# ST_LINK_V2.net
KiCad netlist of a schematic drawn in Altium Designer
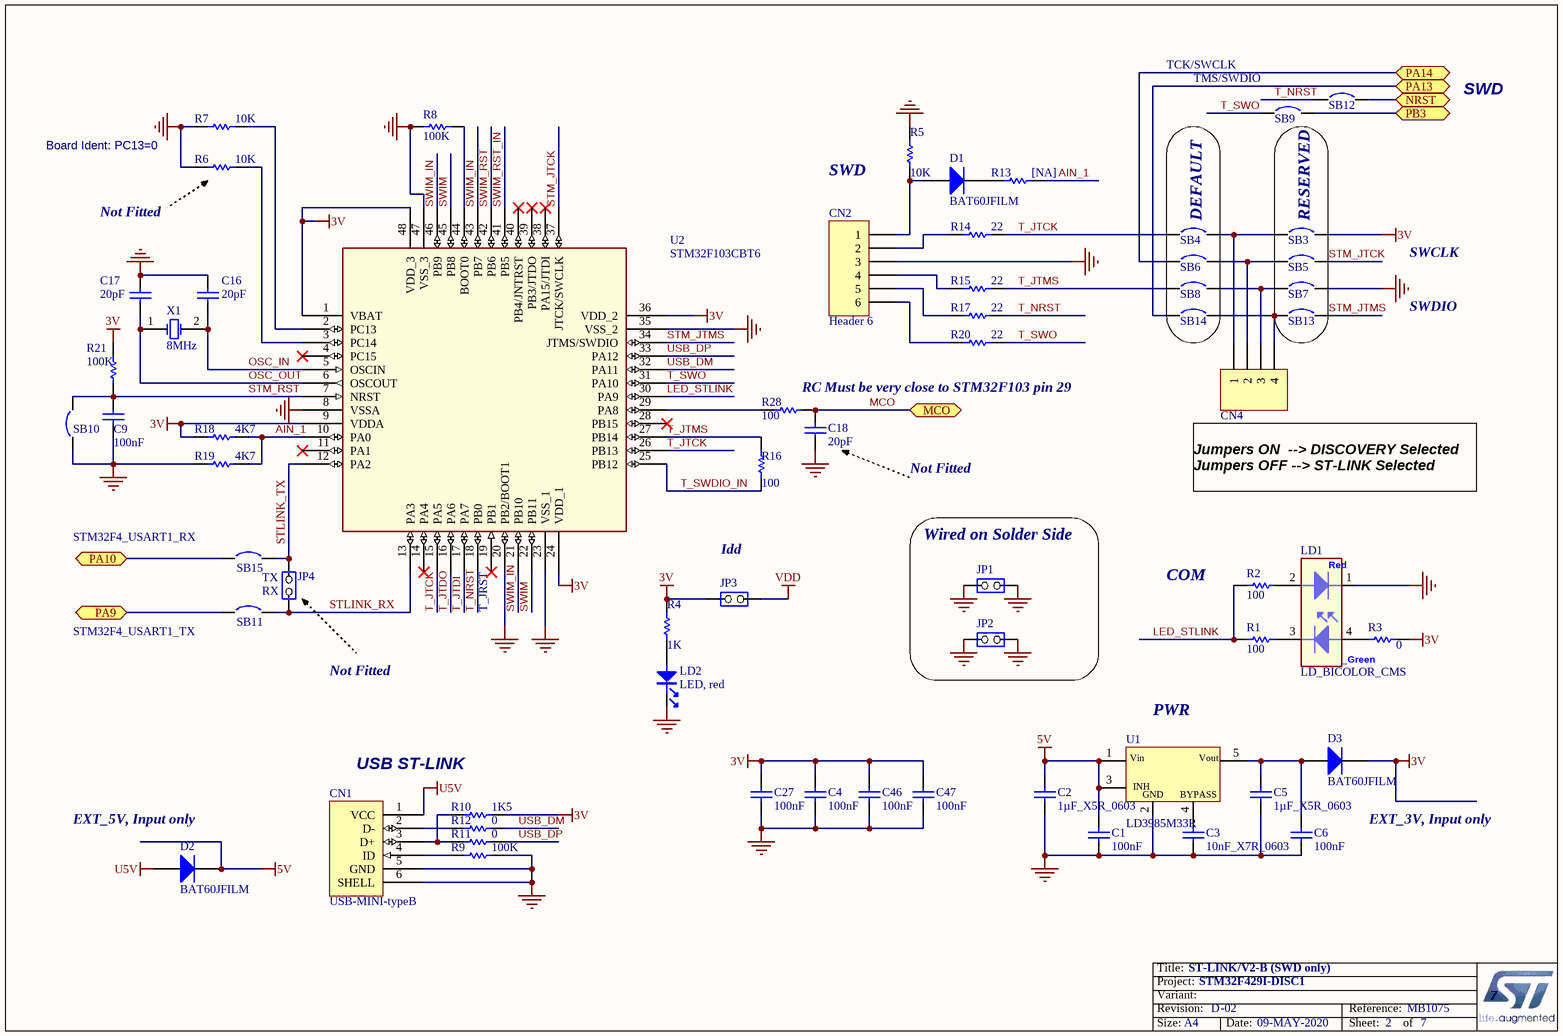
[diagram p0: ST_LINK_V2.SCHDOC]

(export (version "E")
  (design (tool "Eeschema 10.0.6"))
  (components
    (comp (ref "C1")
      (value "100nF")
      (footprint "0402C")
      (description "Capacitor 0402 / 0603 / 0805")
      (libsource (lib "MCD_TOOLS") (part "Capacitor_ST"))
    )
    (comp (ref "C2")
      (value "1µF_X5R_0603")
      (footprint "0603C")
      (description "0603  X5R 1µF")
      (fields (field (name "TOLERANCE") "10%"))
      (libsource (lib "MB963_1") (part "CAP SMD 0603  X5R 1µF 25V 10%"))
    )
    (comp (ref "C3")
      (value "10nF_X7R_0603")
      (footprint "0603C")
      (description "0603  X7R 10NF")
      (fields (field (name "TOLERANCE") "10%"))
      (libsource (lib "MB963_1") (part "CAP SMD 0603  X7R 10000PF 50V 10%"))
    )
    (comp (ref "C4")
      (value "100nF")
      (footprint "0402C")
      (description "Capacitor 0402 / 0603 / 0805")
      (libsource (lib "MCD_TOOLS") (part "Capacitor_ST"))
    )
    (comp (ref "C5")
      (value "1µF_X5R_0603")
      (footprint "0603C")
      (description "0603  X5R 1µF")
      (fields (field (name "TOLERANCE") "10%"))
      (libsource (lib "MB963_1") (part "CAP SMD 0603  X5R 1µF 25V 10%"))
    )
    (comp (ref "C6")
      (value "100nF")
      (footprint "0402C")
      (description "Capacitor 0402 / 0603 / 0805")
      (libsource (lib "MCD_TOOLS") (part "Capacitor_ST"))
    )
    (comp (ref "C9")
      (value "100nF")
      (footprint "0402C")
      (description "Capacitor 0402 / 0603 / 0805")
      (libsource (lib "MCD_TOOLS") (part "Capacitor_ST"))
    )
    (comp (ref "C16")
      (value "20pF")
      (footprint "0402C")
      (description "Capacitor 0402 / 0603 / 0805")
      (libsource (lib "MCD_TOOLS") (part "Capacitor_ST"))
    )
    (comp (ref "C17")
      (value "20pF")
      (footprint "0402C")
      (description "Capacitor 0402 / 0603 / 0805")
      (libsource (lib "MCD_TOOLS") (part "Capacitor_ST"))
    )
    (comp (ref "C18")
      (value "20pF")
      (footprint "0402C")
      (description "Capacitor 0402 / 0603 / 0805")
      (libsource (lib "MCD_TOOLS") (part "Capacitor_ST"))
    )
    (comp (ref "C27")
      (value "100nF")
      (footprint "0402C")
      (description "Capacitor 0402 / 0603 / 0805")
      (libsource (lib "MCD_TOOLS") (part "Capacitor_ST"))
    )
    (comp (ref "C46")
      (value "100nF")
      (footprint "0402C")
      (description "Capacitor 0402 / 0603 / 0805")
      (libsource (lib "MCD_TOOLS") (part "Capacitor_ST"))
    )
    (comp (ref "C47")
      (value "100nF")
      (footprint "0402C")
      (description "Capacitor 0402 / 0603 / 0805")
      (libsource (lib "MCD_TOOLS") (part "Capacitor_ST"))
    )
    (comp (ref "CN1")
      (value "USB-MINI-typeB")
      (footprint "USB-MINI-B-SMD")
      (description "USB-MINI-typeB connector")
      (libsource (lib "MCD_TOOLS") (part "USB-MINI-typeB connector"))
    )
    (comp (ref "CN2")
      (value "Header 6")
      (footprint "HDR1X6")
      (description "Header, 6-Pin")
      (fields (field (name "PUBLISHER") "Altium Limited"))
      (libsource (lib "Miscellaneous Connectors") (part "Header 6"))
    )
    (comp (ref "CN4")
      (value "Header 4")
      (footprint "Header 4")
      (description "Header, 4-Pin")
      (fields (field (name "PUBLISHER") "Altium Limited"))
      (libsource (lib "MB963_1") (part "Header 4"))
    )
    (comp (ref "D1")
      (value "BAT60JFILM")
      (footprint "SOD323/A")
      (libsource (lib "MCD_TOOLS") (part "BAT60JFILM"))
    )
    (comp (ref "D2")
      (value "BAT60JFILM")
      (footprint "SOD323/A")
      (libsource (lib "MCD_TOOLS") (part "BAT60JFILM"))
    )
    (comp (ref "D3")
      (value "BAT60JFILM")
      (footprint "SOD323/A")
      (libsource (lib "MCD_TOOLS") (part "BAT60JFILM"))
    )
    (comp (ref "JP1") (value "~") (footprint "SIP2/2.54") (libsource (lib "*") (part "JP2")))
    (comp (ref "JP2") (value "~") (footprint "SIP2/2.54") (libsource (lib "*") (part "JP2")))
    (comp (ref "JP3") (value "~") (footprint "SIP2/2.54") (libsource (lib "*") (part "JP2")))
    (comp (ref "JP4") (value "JP2") (footprint "SIP2/2.54") (libsource (lib "MCD_TOOLS") (part "JP2")))
    (comp (ref "LD1")
      (value "LD_BICOLOR_CMS")
      (footprint "HSMF-A201")
      (description "Bicolor Led")
      (libsource (lib "MCD_TOOLS") (part "LD_BICOLOR_CMS"))
    )
    (comp (ref "LD2")
      (value "LED, red")
      (footprint "0603D")
      (description "LED, red, 0603")
      (libsource (lib "MCD_TOOLS") (part "LED_red"))
    )
    (comp (ref "R1")
      (value "100")
      (footprint "0402R")
      (description "Resistor 0402 / 0603 / 0805")
      (libsource (lib "MCD_TOOLS") (part "Resistor_ST"))
    )
    (comp (ref "R2")
      (value "100")
      (footprint "0402R")
      (description "Resistor 0402 / 0603 / 0805")
      (libsource (lib "MCD_TOOLS") (part "Resistor_ST"))
    )
    (comp (ref "R3")
      (value "0")
      (footprint "0402R")
      (description "Resistor 0402 / 0603 / 0805")
      (libsource (lib "MCD_TOOLS") (part "Resistor_ST"))
    )
    (comp (ref "R4")
      (value "1K")
      (footprint "0402R")
      (description "Resistor 0402 / 0603 / 0805")
      (libsource (lib "MCD_TOOLS") (part "Resistor_ST"))
    )
    (comp (ref "R5")
      (value "10K")
      (footprint "0402R")
      (description "Resistor 0402 / 0603 / 0805")
      (libsource (lib "MCD_TOOLS") (part "Resistor_ST"))
    )
    (comp (ref "R6")
      (value "10K")
      (footprint "0402R")
      (description "Resistor 0402 / 0603 / 0805")
      (libsource (lib "MCD_TOOLS") (part "Resistor_ST"))
    )
    (comp (ref "R7")
      (value "10K")
      (footprint "0402R")
      (description "Resistor 0402 / 0603 / 0805")
      (libsource (lib "MCD_TOOLS") (part "Resistor_ST"))
    )
    (comp (ref "R8")
      (value "100K")
      (footprint "0402R")
      (description "Resistor 0402 / 0603 / 0805")
      (libsource (lib "MCD_TOOLS") (part "Resistor_ST"))
    )
    (comp (ref "R9")
      (value "100K")
      (footprint "0402R")
      (description "Resistor 0402 / 0603 / 0805")
      (libsource (lib "MCD_TOOLS") (part "Resistor_ST"))
    )
    (comp (ref "R10")
      (value "1K5")
      (footprint "0402R")
      (description "Resistor 0402 / 0603 / 0805")
      (libsource (lib "MCD_TOOLS") (part "Resistor_ST"))
    )
    (comp (ref "R11")
      (value "0")
      (footprint "0402R")
      (description "Resistor 0402 / 0603 / 0805")
      (libsource (lib "MCD_TOOLS") (part "Resistor_ST"))
    )
    (comp (ref "R12")
      (value "0")
      (footprint "0402R")
      (description "Resistor 0402 / 0603 / 0805")
      (libsource (lib "MCD_TOOLS") (part "Resistor_ST"))
    )
    (comp (ref "R13")
      (value "[NA]")
      (footprint "0402R")
      (description "Resistor 0402 / 0603 / 0805")
      (libsource (lib "MCD_TOOLS") (part "Resistor_ST"))
    )
    (comp (ref "R14")
      (value "22")
      (footprint "0402R")
      (description "Resistor 0402 / 0603 / 0805")
      (libsource (lib "MCD_TOOLS") (part "Resistor_ST"))
    )
    (comp (ref "R15")
      (value "22")
      (footprint "0402R")
      (description "Resistor 0402 / 0603 / 0805")
      (libsource (lib "MCD_TOOLS") (part "Resistor_ST"))
    )
    (comp (ref "R16")
      (value "100")
      (footprint "0402R")
      (description "Resistor 0402 / 0603 / 0805")
      (libsource (lib "MCD_TOOLS") (part "Resistor_ST"))
    )
    (comp (ref "R17")
      (value "22")
      (footprint "0402R")
      (description "Resistor 0402 / 0603 / 0805")
      (libsource (lib "MCD_TOOLS") (part "Resistor_ST"))
    )
    (comp (ref "R18")
      (value "4K7")
      (footprint "0402R")
      (description "Resistor 0402 / 0603 / 0805")
      (libsource (lib "MCD_TOOLS") (part "Resistor_ST"))
    )
    (comp (ref "R19")
      (value "4K7")
      (footprint "0402R")
      (description "Resistor 0402 / 0603 / 0805")
      (libsource (lib "MCD_TOOLS") (part "Resistor_ST"))
    )
    (comp (ref "R20")
      (value "22")
      (footprint "0402R")
      (description "Resistor 0402 / 0603 / 0805")
      (libsource (lib "MCD_TOOLS") (part "Resistor_ST"))
    )
    (comp (ref "R21")
      (value "100K")
      (footprint "0402R")
      (description "Resistor 0402 / 0603 / 0805")
      (libsource (lib "MCD_TOOLS") (part "Resistor_ST"))
    )
    (comp (ref "R28")
      (value "100")
      (footprint "0402R")
      (description "Resistor 0402 / 0603 / 0805")
      (libsource (lib "MCD_TOOLS") (part "Resistor_ST"))
    )
    (comp (ref "SB3")
      (value "Circuit Breaker")
      (footprint "JP2_SMD")
      (fields (field (name "PUBLISHER") "Altium Limited"))
      (libsource (lib "MB915") (part "Circuit Breaker"))
    )
    (comp (ref "SB4")
      (value "Circuit Breaker")
      (footprint "JP2_SMD")
      (fields (field (name "PUBLISHER") "Altium Limited"))
      (libsource (lib "MB915") (part "Circuit Breaker"))
    )
    (comp (ref "SB5")
      (value "Circuit Breaker")
      (footprint "JP2_SMD")
      (fields (field (name "PUBLISHER") "Altium Limited"))
      (libsource (lib "MB915") (part "Circuit Breaker"))
    )
    (comp (ref "SB6")
      (value "Circuit Breaker")
      (footprint "JP2_SMD")
      (fields (field (name "PUBLISHER") "Altium Limited"))
      (libsource (lib "MB915") (part "Circuit Breaker"))
    )
    (comp (ref "SB7")
      (value "Circuit Breaker")
      (footprint "JP2_SMD")
      (fields (field (name "PUBLISHER") "Altium Limited"))
      (libsource (lib "MB915") (part "Circuit Breaker"))
    )
    (comp (ref "SB8")
      (value "Circuit Breaker")
      (footprint "JP2_SMD")
      (fields (field (name "PUBLISHER") "Altium Limited"))
      (libsource (lib "MB915") (part "Circuit Breaker"))
    )
    (comp (ref "SB9")
      (value "Circuit Breaker")
      (footprint "JP2_SMD")
      (fields (field (name "PUBLISHER") "Altium Limited"))
      (libsource (lib "MCD_TOOLS") (part "Circuit Breaker"))
    )
    (comp (ref "SB10")
      (value "Circuit Breaker")
      (footprint "JP2_SMD")
      (fields (field (name "PUBLISHER") "Altium Limited"))
      (libsource (lib "MB915") (part "Circuit Breaker"))
    )
    (comp (ref "SB11")
      (value "Circuit Breaker")
      (footprint "JP2_SMD")
      (fields (field (name "PUBLISHER") "Altium Limited"))
      (libsource (lib "MCD_TOOLS") (part "Circuit Breaker"))
    )
    (comp (ref "SB12")
      (value "Circuit Breaker")
      (footprint "JP2_SMD")
      (fields (field (name "PUBLISHER") "Altium Limited"))
      (libsource (lib "MB915") (part "Circuit Breaker"))
    )
    (comp (ref "SB13")
      (value "Circuit Breaker")
      (footprint "JP2_SMD")
      (fields (field (name "PUBLISHER") "Altium Limited"))
      (libsource (lib "MB915") (part "Circuit Breaker"))
    )
    (comp (ref "SB14")
      (value "Circuit Breaker")
      (footprint "JP2_SMD")
      (fields (field (name "PUBLISHER") "Altium Limited"))
      (libsource (lib "MB915") (part "Circuit Breaker"))
    )
    (comp (ref "SB15")
      (value "Circuit Breaker")
      (footprint "JP2_SMD")
      (fields (field (name "PUBLISHER") "Altium Limited"))
      (libsource (lib "MCD_TOOLS") (part "Circuit Breaker"))
    )
    (comp (ref "U1")
      (value "LD3985M33R")
      (footprint "SOT-23-5L")
      (description "Ultra low drop-low noise BiCMOS voltage, regulators low ESR capacitors compatible")
      (libsource (lib "MCD_TOOLS") (part "LD3985M33R"))
    )
    (comp (ref "U2")
      (value "STM32F103CBT6")
      (footprint "QFP48 7x7")
      (description "Medium-density performance line ARM-based 32-bit MCU with 128KB Flash")
      (libsource (lib "MCD_TOOLS") (part "STM32F103CBT6"))
    )
    (comp (ref "X1")
      (value "8MHz")
      (footprint "XTAL1")
      (description "Crystal Oscillator,8Mhz,20PF,20PPM,-10-70 degree,DIP,HC-49S")
      (libsource (lib "MCD_TOOLS") (part "XTAL"))
    )
  )
  (nets
    (net (code "1") (name "/AIN_1") (class "Default")
      (node (ref "R13") (pin "2") (pinfunction "2_2") (pintype "passive"))
      (node (ref "R18") (pin "2") (pinfunction "2_2") (pintype "passive"))
      (node (ref "R19") (pin "2") (pinfunction "2_2") (pintype "passive"))
      (node (ref "U2") (pin "10") (pinfunction "PA0_10") (pintype "bidirectional"))
    )
    (net (code "2") (name "/LED_STLINK") (class "Default")
      (node (ref "R1") (pin "1") (pinfunction "1_1") (pintype "passive"))
      (node (ref "R2") (pin "1") (pinfunction "1_1") (pintype "passive"))
      (node (ref "U2") (pin "30") (pinfunction "PA9_30") (pintype "bidirectional"))
    )
    (net (code "3") (name "/MCO") (class "Default")
      (node (ref "C18") (pin "2") (pinfunction "2_2") (pintype "passive"))
      (node (ref "R28") (pin "2") (pinfunction "2_2") (pintype "passive"))
    )
    (net (code "4") (name "/NRST") (class "Default")
      (node (ref "SB12") (pin "2") (pinfunction "2_2") (pintype "passive"))
    )
    (net (code "5") (name "/OSC_IN") (class "Default")
      (node (ref "C16") (pin "1") (pinfunction "1_1") (pintype "passive"))
      (node (ref "U2") (pin "5") (pinfunction "OSCIN_5") (pintype "input"))
      (node (ref "X1") (pin "2") (pinfunction "OSC2_2") (pintype "passive"))
    )
    (net (code "6") (name "/OSC_OUT") (class "Default")
      (node (ref "C17") (pin "1") (pinfunction "1_1") (pintype "passive"))
      (node (ref "U2") (pin "6") (pinfunction "OSCOUT_6") (pintype "output"))
      (node (ref "X1") (pin "1") (pinfunction "OSC1_1") (pintype "passive"))
    )
    (net (code "7") (name "/PA9") (class "Default")
      (node (ref "SB11") (pin "1") (pinfunction "1_1") (pintype "passive"))
    )
    (net (code "8") (name "/PA10") (class "Default")
      (node (ref "SB15") (pin "1") (pinfunction "1_1") (pintype "passive"))
    )
    (net (code "9") (name "/PA13") (class "Default")
      (node (ref "SB14") (pin "1") (pinfunction "1_1") (pintype "passive"))
    )
    (net (code "10") (name "/PA14") (class "Default")
      (node (ref "SB6") (pin "1") (pinfunction "1_1") (pintype "passive"))
    )
    (net (code "11") (name "/PB3") (class "Default")
      (node (ref "SB9") (pin "2") (pinfunction "2_2") (pintype "passive"))
    )
    (net (code "12") (name "/STLINK_RX") (class "Default")
      (node (ref "JP4") (pin "1") (pinfunction "COMMON_1") (pintype "passive"))
      (node (ref "SB11") (pin "2") (pinfunction "2_2") (pintype "passive"))
      (node (ref "U2") (pin "13") (pinfunction "PA3_13") (pintype "bidirectional"))
    )
    (net (code "13") (name "/STLINK_TX") (class "Default")
      (node (ref "JP4") (pin "2") (pinfunction "NO_2") (pintype "passive"))
      (node (ref "SB15") (pin "2") (pinfunction "2_2") (pintype "passive"))
      (node (ref "U2") (pin "12") (pinfunction "PA2_12") (pintype "bidirectional"))
    )
    (net (code "14") (name "/STM_JTCK") (class "Default")
      (node (ref "SB5") (pin "2") (pinfunction "2_2") (pintype "passive"))
      (node (ref "U2") (pin "37") (pinfunction "JTCK/SWCLK_37") (pintype "bidirectional"))
    )
    (net (code "15") (name "/STM_JTMS") (class "Default")
      (node (ref "SB13") (pin "2") (pinfunction "2_2") (pintype "passive"))
      (node (ref "U2") (pin "34") (pinfunction "JTMS/SWDIO_34") (pintype "bidirectional"))
    )
    (net (code "16") (name "/STM_RST") (class "Default")
      (node (ref "C9") (pin "2") (pinfunction "2_2") (pintype "passive"))
      (node (ref "R21") (pin "1") (pinfunction "1_1") (pintype "passive"))
      (node (ref "SB10") (pin "2") (pinfunction "2_2") (pintype "passive"))
      (node (ref "U2") (pin "7") (pinfunction "NRST_7") (pintype "input"))
    )
    (net (code "17") (name "/SWIM") (class "Default")
      (node (ref "U2") (pin "22") (pinfunction "PB11_22") (pintype "bidirectional"))
      (node (ref "U2") (pin "45") (pinfunction "PB8_45") (pintype "bidirectional"))
    )
    (net (code "18") (name "/SWIM_IN") (class "Default")
      (node (ref "U2") (pin "21") (pinfunction "PB10_21") (pintype "bidirectional"))
      (node (ref "U2") (pin "43") (pinfunction "PB7_43") (pintype "bidirectional"))
      (node (ref "U2") (pin "46") (pinfunction "PB9_46") (pintype "bidirectional"))
    )
    (net (code "19") (name "/SWIM_RST") (class "Default")
      (node (ref "U2") (pin "42") (pinfunction "PB6_42") (pintype "bidirectional"))
    )
    (net (code "20") (name "/SWIM_RST_IN") (class "Default")
      (node (ref "U2") (pin "41") (pinfunction "PB5_41") (pintype "bidirectional"))
    )
    (net (code "21") (name "/T_JTCK") (class "Default")
      (node (ref "R14") (pin "2") (pinfunction "2_2") (pintype "passive"))
      (node (ref "SB4") (pin "1") (pinfunction "1_1") (pintype "passive"))
      (node (ref "U2") (pin "15") (pinfunction "PA5_15") (pintype "bidirectional"))
      (node (ref "U2") (pin "26") (pinfunction "PB13_26") (pintype "bidirectional"))
    )
    (net (code "22") (name "/T_JTDI") (class "Default")
      (node (ref "U2") (pin "17") (pinfunction "PA7_17") (pintype "bidirectional"))
    )
    (net (code "23") (name "/T_JTDO") (class "Default")
      (node (ref "U2") (pin "16") (pinfunction "PA6_16") (pintype "bidirectional"))
    )
    (net (code "24") (name "/T_JTMS") (class "Default")
      (node (ref "R15") (pin "2") (pinfunction "2_2") (pintype "passive"))
      (node (ref "R16") (pin "2") (pinfunction "2_2") (pintype "passive"))
      (node (ref "SB8") (pin "1") (pinfunction "1_1") (pintype "passive"))
      (node (ref "U2") (pin "27") (pinfunction "PB14_27") (pintype "bidirectional"))
    )
    (net (code "25") (name "/T_NRST") (class "Default")
      (node (ref "R17") (pin "2") (pinfunction "2_2") (pintype "passive"))
      (node (ref "SB12") (pin "1") (pinfunction "1_1") (pintype "passive"))
      (node (ref "U2") (pin "18") (pinfunction "PB0_18") (pintype "bidirectional"))
    )
    (net (code "26") (name "/T_SWDIO_IN") (class "Default")
      (node (ref "R16") (pin "1") (pinfunction "1_1") (pintype "passive"))
      (node (ref "U2") (pin "25") (pinfunction "PB12_25") (pintype "bidirectional"))
    )
    (net (code "27") (name "/T_SWO") (class "Default")
      (node (ref "R20") (pin "2") (pinfunction "2_2") (pintype "passive"))
      (node (ref "SB9") (pin "1") (pinfunction "1_1") (pintype "passive"))
      (node (ref "U2") (pin "31") (pinfunction "PA10_31") (pintype "bidirectional"))
    )
    (net (code "28") (name "/USB_DM") (class "Default")
      (node (ref "R12") (pin "2") (pinfunction "2_2") (pintype "passive"))
      (node (ref "U2") (pin "32") (pinfunction "PA11_32") (pintype "bidirectional"))
    )
    (net (code "29") (name "/USB_DP") (class "Default")
      (node (ref "R11") (pin "2") (pinfunction "2_2") (pintype "passive"))
      (node (ref "U2") (pin "33") (pinfunction "PA12_33") (pintype "bidirectional"))
    )
    (net (code "30") (name "3V") (class "Default")
      (node (ref "C27") (pin "2") (pinfunction "2_2") (pintype "passive"))
      (node (ref "C4") (pin "2") (pinfunction "2_2") (pintype "passive"))
      (node (ref "C46") (pin "2") (pinfunction "2_2") (pintype "passive"))
      (node (ref "C47") (pin "2") (pinfunction "2_2") (pintype "passive"))
      (node (ref "D3") (pin "2") (pinfunction "K_2") (pintype "passive"))
      (node (ref "JP3") (pin "1") (pinfunction "COMMON_1") (pintype "passive"))
      (node (ref "R10") (pin "2") (pinfunction "2_2") (pintype "passive"))
      (node (ref "R18") (pin "1") (pinfunction "1_1") (pintype "passive"))
      (node (ref "R21") (pin "2") (pinfunction "2_2") (pintype "passive"))
      (node (ref "R3") (pin "2") (pinfunction "2_2") (pintype "passive"))
      (node (ref "R4") (pin "2") (pinfunction "2_2") (pintype "passive"))
      (node (ref "SB3") (pin "2") (pinfunction "2_2") (pintype "passive"))
      (node (ref "U2") (pin "1") (pinfunction "VBAT_1") (pintype "power_in"))
      (node (ref "U2") (pin "24") (pinfunction "VDD_1_24") (pintype "power_in"))
      (node (ref "U2") (pin "36") (pinfunction "VDD_2_36") (pintype "power_in"))
      (node (ref "U2") (pin "48") (pinfunction "VDD_3_48") (pintype "power_in"))
      (node (ref "U2") (pin "9") (pinfunction "VDDA_9") (pintype "power_in"))
    )
    (net (code "31") (name "5V") (class "Default")
      (node (ref "C1") (pin "2") (pinfunction "2_2") (pintype "passive"))
      (node (ref "C2") (pin "2") (pinfunction "2_2") (pintype "passive"))
      (node (ref "D2") (pin "2") (pinfunction "K_2") (pintype "passive"))
      (node (ref "U1") (pin "1") (pinfunction "Vin_1") (pintype "passive"))
      (node (ref "U1") (pin "3") (pinfunction "CE_3") (pintype "passive"))
    )
    (net (code "32") (name "GND") (class "Default")
      (node (ref "C1") (pin "1") (pinfunction "1_1") (pintype "passive"))
      (node (ref "C16") (pin "2") (pinfunction "2_2") (pintype "passive"))
      (node (ref "C17") (pin "2") (pinfunction "2_2") (pintype "passive"))
      (node (ref "C18") (pin "1") (pinfunction "1_1") (pintype "passive"))
      (node (ref "C2") (pin "1") (pinfunction "1_1") (pintype "passive"))
      (node (ref "C27") (pin "1") (pinfunction "1_1") (pintype "passive"))
      (node (ref "C3") (pin "1") (pinfunction "1_1") (pintype "passive"))
      (node (ref "C4") (pin "1") (pinfunction "1_1") (pintype "passive"))
      (node (ref "C46") (pin "1") (pinfunction "1_1") (pintype "passive"))
      (node (ref "C47") (pin "1") (pinfunction "1_1") (pintype "passive"))
      (node (ref "C5") (pin "2") (pinfunction "2_2") (pintype "passive"))
      (node (ref "C6") (pin "1") (pinfunction "1_1") (pintype "passive"))
      (node (ref "C9") (pin "1") (pinfunction "1_1") (pintype "passive"))
      (node (ref "CN1") (pin "5") (pinfunction "GND_5") (pintype "passive"))
      (node (ref "CN1") (pin "6") (pinfunction "SHELL_6") (pintype "passive"))
      (node (ref "CN2") (pin "3") (pinfunction "3_3") (pintype "passive"))
      (node (ref "JP1") (pin "1") (pinfunction "COMMON_1") (pintype "passive"))
      (node (ref "JP1") (pin "2") (pinfunction "NO_2") (pintype "passive"))
      (node (ref "JP2") (pin "1") (pinfunction "COMMON_1") (pintype "passive"))
      (node (ref "JP2") (pin "2") (pinfunction "NO_2") (pintype "passive"))
      (node (ref "LD1") (pin "1") (pinfunction "1_1") (pintype "passive"))
      (node (ref "LD2") (pin "2") (pintype "passive"))
      (node (ref "R19") (pin "1") (pinfunction "1_1") (pintype "passive"))
      (node (ref "R5") (pin "2") (pinfunction "2_2") (pintype "passive"))
      (node (ref "R6") (pin "1") (pinfunction "1_1") (pintype "passive"))
      (node (ref "R7") (pin "1") (pinfunction "1_1") (pintype "passive"))
      (node (ref "R8") (pin "1") (pinfunction "1_1") (pintype "passive"))
      (node (ref "R9") (pin "2") (pinfunction "2_2") (pintype "passive"))
      (node (ref "SB10") (pin "1") (pinfunction "1_1") (pintype "passive"))
      (node (ref "SB7") (pin "2") (pinfunction "2_2") (pintype "passive"))
      (node (ref "U1") (pin "2") (pinfunction "GND_2") (pintype "passive"))
      (node (ref "U2") (pin "20") (pinfunction "PB2/BOOT1_20") (pintype "bidirectional"))
      (node (ref "U2") (pin "23") (pinfunction "VSS_1_23") (pintype "power_in"))
      (node (ref "U2") (pin "35") (pinfunction "VSS_2_35") (pintype "power_in"))
      (node (ref "U2") (pin "47") (pinfunction "VSS_3_47") (pintype "power_in"))
      (node (ref "U2") (pin "8") (pinfunction "VSSA_8") (pintype "power_in"))
    )
    (net (code "33") (name "Net-(CN1-D+)") (class "Default")
      (node (ref "CN1") (pin "3") (pinfunction "D+_3") (pintype "bidirectional"))
      (node (ref "R10") (pin "1") (pinfunction "1_1") (pintype "passive"))
      (node (ref "R11") (pin "1") (pinfunction "1_1") (pintype "passive"))
    )
    (net (code "34") (name "Net-(CN1-D-)") (class "Default")
      (node (ref "CN1") (pin "2") (pinfunction "D-_2") (pintype "bidirectional"))
      (node (ref "R12") (pin "1") (pinfunction "1_1") (pintype "passive"))
    )
    (net (code "35") (name "Net-(CN1-ID)") (class "Default")
      (node (ref "CN1") (pin "4") (pinfunction "ID_4") (pintype "input"))
      (node (ref "R9") (pin "1") (pinfunction "1_1") (pintype "passive"))
    )
    (net (code "36") (name "Net-(CN2-Pad2)") (class "Default")
      (node (ref "CN2") (pin "2") (pinfunction "2_2") (pintype "passive"))
      (node (ref "R14") (pin "1") (pinfunction "1_1") (pintype "passive"))
    )
    (net (code "37") (name "Net-(CN2-Pad4)") (class "Default")
      (node (ref "CN2") (pin "4") (pinfunction "4_4") (pintype "passive"))
      (node (ref "R15") (pin "1") (pinfunction "1_1") (pintype "passive"))
    )
    (net (code "38") (name "Net-(CN2-Pad5)") (class "Default")
      (node (ref "CN2") (pin "5") (pinfunction "5_5") (pintype "passive"))
      (node (ref "R17") (pin "1") (pinfunction "1_1") (pintype "passive"))
    )
    (net (code "39") (name "Net-(CN2-Pad6)") (class "Default")
      (node (ref "CN2") (pin "6") (pinfunction "6_6") (pintype "passive"))
      (node (ref "R20") (pin "1") (pinfunction "1_1") (pintype "passive"))
    )
    (net (code "40") (name "Net-(CN4-Pad1)") (class "Default")
      (node (ref "CN4") (pin "1") (pinfunction "1_1") (pintype "passive"))
      (node (ref "SB3") (pin "1") (pinfunction "1_1") (pintype "passive"))
      (node (ref "SB4") (pin "2") (pinfunction "2_2") (pintype "passive"))
    )
    (net (code "41") (name "Net-(CN4-Pad2)") (class "Default")
      (node (ref "CN4") (pin "2") (pinfunction "2_2") (pintype "passive"))
      (node (ref "SB5") (pin "1") (pinfunction "1_1") (pintype "passive"))
      (node (ref "SB6") (pin "2") (pinfunction "2_2") (pintype "passive"))
    )
    (net (code "42") (name "Net-(CN4-Pad3)") (class "Default")
      (node (ref "CN4") (pin "3") (pinfunction "3_3") (pintype "passive"))
      (node (ref "SB7") (pin "1") (pinfunction "1_1") (pintype "passive"))
      (node (ref "SB8") (pin "2") (pinfunction "2_2") (pintype "passive"))
    )
    (net (code "43") (name "Net-(CN4-Pad4)") (class "Default")
      (node (ref "CN4") (pin "4") (pinfunction "4_4") (pintype "passive"))
      (node (ref "SB13") (pin "1") (pinfunction "1_1") (pintype "passive"))
      (node (ref "SB14") (pin "2") (pinfunction "2_2") (pintype "passive"))
    )
    (net (code "44") (name "Net-(D1-A)") (class "Default")
      (node (ref "CN2") (pin "1") (pinfunction "1_1") (pintype "passive"))
      (node (ref "D1") (pin "1") (pinfunction "A_1") (pintype "passive"))
      (node (ref "R5") (pin "1") (pinfunction "1_1") (pintype "passive"))
    )
    (net (code "45") (name "Net-(D1-K)") (class "Default")
      (node (ref "D1") (pin "2") (pinfunction "K_2") (pintype "passive"))
      (node (ref "R13") (pin "1") (pinfunction "1_1") (pintype "passive"))
    )
    (net (code "46") (name "Net-(D3-A)") (class "Default")
      (node (ref "C5") (pin "1") (pinfunction "1_1") (pintype "passive"))
      (node (ref "C6") (pin "2") (pinfunction "2_2") (pintype "passive"))
      (node (ref "D3") (pin "1") (pinfunction "A_1") (pintype "passive"))
      (node (ref "U1") (pin "5") (pinfunction "Vout_5") (pintype "passive"))
    )
    (net (code "47") (name "Net-(LD1-Pad2)") (class "Default")
      (node (ref "LD1") (pin "2") (pinfunction "2_2") (pintype "passive"))
      (node (ref "R2") (pin "2") (pinfunction "2_2") (pintype "passive"))
    )
    (net (code "48") (name "Net-(LD1-Pad3)") (class "Default")
      (node (ref "LD1") (pin "3") (pinfunction "3_3") (pintype "passive"))
      (node (ref "R1") (pin "2") (pinfunction "2_2") (pintype "passive"))
    )
    (net (code "49") (name "Net-(LD1-Pad4)") (class "Default")
      (node (ref "LD1") (pin "4") (pinfunction "4_4") (pintype "passive"))
      (node (ref "R3") (pin "1") (pinfunction "1_1") (pintype "passive"))
    )
    (net (code "50") (name "Net-(LD2-Pad1)") (class "Default")
      (node (ref "LD2") (pin "1") (pintype "passive"))
      (node (ref "R4") (pin "1") (pinfunction "1_1") (pintype "passive"))
    )
    (net (code "51") (name "Net-(U1-BYPASS)") (class "Default")
      (node (ref "C3") (pin "2") (pinfunction "2_2") (pintype "passive"))
      (node (ref "U1") (pin "4") (pinfunction "BYPASS_4") (pintype "passive"))
    )
    (net (code "52") (name "Net-(U2-BOOT0)") (class "Default")
      (node (ref "R8") (pin "2") (pinfunction "2_2") (pintype "passive"))
      (node (ref "U2") (pin "44") (pinfunction "BOOT0_44") (pintype "bidirectional"))
    )
    (net (code "53") (name "Net-(U2-PA8)") (class "Default")
      (node (ref "R28") (pin "1") (pinfunction "1_1") (pintype "passive"))
      (node (ref "U2") (pin "29") (pinfunction "PA8_29") (pintype "bidirectional"))
    )
    (net (code "54") (name "Net-(U2-PC13)") (class "Default")
      (node (ref "R7") (pin "2") (pinfunction "2_2") (pintype "passive"))
      (node (ref "U2") (pin "2") (pinfunction "PC13_2") (pintype "bidirectional"))
    )
    (net (code "55") (name "Net-(U2-PC14)") (class "Default")
      (node (ref "R6") (pin "2") (pinfunction "2_2") (pintype "passive"))
      (node (ref "U2") (pin "3") (pinfunction "PC14_3") (pintype "bidirectional"))
    )
    (net (code "56") (name "U5V") (class "Default")
      (node (ref "CN1") (pin "1") (pinfunction "VCC_1") (pintype "power_in"))
      (node (ref "D2") (pin "1") (pinfunction "A_1") (pintype "passive"))
    )
    (net (code "57") (name "VDD") (class "Default")
      (node (ref "JP3") (pin "2") (pinfunction "NO_2") (pintype "passive"))
    )
    (net (code "58") (name "unconnected-(U2-PA1-Pad11)") (class "Default")
      (node (ref "U2") (pin "11") (pinfunction "PA1_11") (pintype "bidirectional+no_connect"))
    )
    (net (code "59") (name "unconnected-(U2-PA4-Pad14)") (class "Default")
      (node (ref "U2") (pin "14") (pinfunction "PA4_14") (pintype "bidirectional+no_connect"))
    )
    (net (code "60") (name "unconnected-(U2-PA15{slash}JTDI-Pad38)") (class "Default")
      (node (ref "U2") (pin "38") (pinfunction "PA15/JTDI_38") (pintype "bidirectional+no_connect"))
    )
    (net (code "61") (name "unconnected-(U2-PB1-Pad19)") (class "Default")
      (node (ref "U2") (pin "19") (pinfunction "PB1_19") (pintype "input+no_connect"))
    )
    (net (code "62") (name "unconnected-(U2-PB3{slash}JTDO-Pad39)") (class "Default")
      (node (ref "U2") (pin "39") (pinfunction "PB3/JTDO_39") (pintype "bidirectional+no_connect"))
    )
    (net (code "63") (name "unconnected-(U2-PB4{slash}JNTRST-Pad40)") (class "Default")
      (node (ref "U2") (pin "40") (pinfunction "PB4/JNTRST_40") (pintype "bidirectional+no_connect"))
    )
    (net (code "64") (name "unconnected-(U2-PB15-Pad28)") (class "Default")
      (node (ref "U2") (pin "28") (pinfunction "PB15_28") (pintype "bidirectional+no_connect"))
    )
    (net (code "65") (name "unconnected-(U2-PC15-Pad4)") (class "Default")
      (node (ref "U2") (pin "4") (pinfunction "PC15_4") (pintype "bidirectional+no_connect"))
    )
  )
)
